# shunts_and_amplifiers.net
KiCad netlist of a schematic drawn in Altium Designer
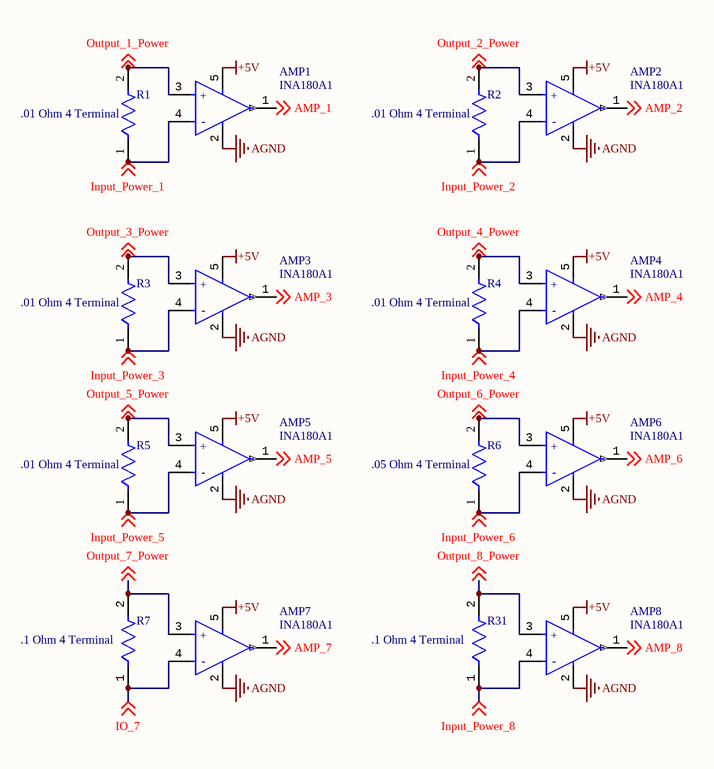
[diagram p0: shunts_and_amplifiers.SchDoc]

(export (version "E")
  (design (tool "Eeschema 10.0.6"))
  (components
    (comp (ref "AMP1")
      (value "INA180A1")
      (footprint "FP-DBV0005A-IPC_A")
      (description "IC CURR SENSE 1 CIRCUIT SOT23-5")
      (libsource (lib "Altium Content Vault") (part "0a55cf1a948ad01a3239aec1b7efad0"))
    )
    (comp (ref "AMP2")
      (value "INA180A1")
      (footprint "FP-DBV0005A-IPC_A")
      (description "IC CURR SENSE 1 CIRCUIT SOT23-5")
      (libsource (lib "Altium Content Vault") (part "0a55cf1a948ad01a3239aec1b7efad0"))
    )
    (comp (ref "AMP3")
      (value "INA180A1")
      (footprint "FP-DBV0005A-IPC_A")
      (description "IC CURR SENSE 1 CIRCUIT SOT23-5")
      (libsource (lib "Altium Content Vault") (part "0a55cf1a948ad01a3239aec1b7efad0"))
    )
    (comp (ref "AMP4")
      (value "INA180A1")
      (footprint "FP-DBV0005A-IPC_A")
      (description "IC CURR SENSE 1 CIRCUIT SOT23-5")
      (libsource (lib "Altium Content Vault") (part "0a55cf1a948ad01a3239aec1b7efad0"))
    )
    (comp (ref "AMP5")
      (value "INA180A1")
      (footprint "FP-DBV0005A-IPC_A")
      (description "IC CURR SENSE 1 CIRCUIT SOT23-5")
      (libsource (lib "Altium Content Vault") (part "0a55cf1a948ad01a3239aec1b7efad0"))
    )
    (comp (ref "AMP6")
      (value "INA180A1")
      (footprint "FP-DBV0005A-IPC_A")
      (description "IC CURR SENSE 1 CIRCUIT SOT23-5")
      (libsource (lib "Altium Content Vault") (part "0a55cf1a948ad01a3239aec1b7efad0"))
    )
    (comp (ref "AMP7")
      (value "INA180A1")
      (footprint "FP-DBV0005A-IPC_A")
      (description "IC CURR SENSE 1 CIRCUIT SOT23-5")
      (libsource (lib "Altium Content Vault") (part "0a55cf1a948ad01a3239aec1b7efad0"))
    )
    (comp (ref "AMP8")
      (value "INA180A1")
      (footprint "FP-DBV0005A-IPC_A")
      (description "IC CURR SENSE 1 CIRCUIT SOT23-5")
      (libsource (lib "Altium Content Vault") (part "0a55cf1a948ad01a3239aec1b7efad0"))
    )
    (comp (ref "R1")
      (value ".01 Ohm 4 Terminal")
      (footprint "FP-WSR3-MFG")
      (description "WSR3R0500FEA Res Metal Strip 4527 0.05 Ohm 1% 3W ±75ppm/°C Molded SMD SMD Embossed Plastic T/R")
      (fields (field (name "TOLERANCE") "1%"))
      (libsource (lib "Altium Content Vault") (part "1029c3af85768c4190bb7ad29bc67b5"))
    )
    (comp (ref "R2")
      (value ".01 Ohm 4 Terminal")
      (footprint "FP-WSR3-MFG")
      (description "WSR3R0500FEA Res Metal Strip 4527 0.05 Ohm 1% 3W ±75ppm/°C Molded SMD SMD Embossed Plastic T/R")
      (fields (field (name "TOLERANCE") "1%"))
      (libsource (lib "Altium Content Vault") (part "1029c3af85768c4190bb7ad29bc67b5"))
    )
    (comp (ref "R3")
      (value ".01 Ohm 4 Terminal")
      (footprint "FP-WSR3-MFG")
      (description "WSR3R0500FEA Res Metal Strip 4527 0.05 Ohm 1% 3W ±75ppm/°C Molded SMD SMD Embossed Plastic T/R")
      (fields (field (name "TOLERANCE") "1%"))
      (libsource (lib "Altium Content Vault") (part "1029c3af85768c4190bb7ad29bc67b5"))
    )
    (comp (ref "R4")
      (value ".01 Ohm 4 Terminal")
      (footprint "FP-WSR3-MFG")
      (description "WSR3R0500FEA Res Metal Strip 4527 0.05 Ohm 1% 3W ±75ppm/°C Molded SMD SMD Embossed Plastic T/R")
      (fields (field (name "TOLERANCE") "1%"))
      (libsource (lib "Altium Content Vault") (part "1029c3af85768c4190bb7ad29bc67b5"))
    )
    (comp (ref "R5")
      (value ".01 Ohm 4 Terminal")
      (footprint "FP-WSR3-MFG")
      (description "WSR3R0500FEA Res Metal Strip 4527 0.05 Ohm 1% 3W ±75ppm/°C Molded SMD SMD Embossed Plastic T/R")
      (fields (field (name "TOLERANCE") "1%"))
      (libsource (lib "Altium Content Vault") (part "1029c3af85768c4190bb7ad29bc67b5"))
    )
    (comp (ref "R6")
      (value ".05 Ohm 4 Terminal")
      (footprint "FP-WSR3-MFG")
      (description "WSR3R0500FEA Res Metal Strip 4527 0.05 Ohm 1% 3W ±75ppm/°C Molded SMD SMD Embossed Plastic T/R")
      (fields (field (name "TOLERANCE") "1%"))
      (libsource (lib "Altium Content Vault") (part "1029c3af85768c4190bb7ad29bc67b5"))
    )
    (comp (ref "R7")
      (value ".1 Ohm 4 Terminal")
      (footprint "FP-WSR-MFG")
      (description "RES 0.1 OHM 1% 3W 4527\r\nWSR3R1000FEK")
      (fields (field (name "MANUFACTURER PART NUMBER") "WSR3R1000FEK") (field (name "TOLERANCE") "1%"))
      (libsource (lib "Altium Content Vault") (part "1029c3af85768c4190bb7ad29bc67b5"))
    )
    (comp (ref "R31")
      (value ".1 Ohm 4 Terminal")
      (footprint "FP-WSR-MFG")
      (description "RES 0.1 OHM 1% 3W 4527\r\nWSR3R1000FEK")
      (fields (field (name "MANUFACTURER PART NUMBER") "WSR3R1000FEK") (field (name "TOLERANCE") "1%"))
      (libsource (lib "Altium Content Vault") (part "1029c3af85768c4190bb7ad29bc67b5"))
    )
  )
  (nets
    (net (code "1") (name "+5V") (class "Default")
      (node (ref "AMP1") (pin "5") (pinfunction "VS_5") (pintype "power_in"))
      (node (ref "AMP2") (pin "5") (pinfunction "VS_5") (pintype "power_in"))
      (node (ref "AMP3") (pin "5") (pinfunction "VS_5") (pintype "power_in"))
      (node (ref "AMP4") (pin "5") (pinfunction "VS_5") (pintype "power_in"))
      (node (ref "AMP5") (pin "5") (pinfunction "VS_5") (pintype "power_in"))
      (node (ref "AMP6") (pin "5") (pinfunction "VS_5") (pintype "power_in"))
      (node (ref "AMP7") (pin "5") (pinfunction "VS_5") (pintype "power_in"))
      (node (ref "AMP8") (pin "5") (pinfunction "VS_5") (pintype "power_in"))
    )
    (net (code "2") (name "AGND") (class "Default")
      (node (ref "AMP1") (pin "2") (pinfunction "GND_2") (pintype "power_in"))
      (node (ref "AMP2") (pin "2") (pinfunction "GND_2") (pintype "power_in"))
      (node (ref "AMP3") (pin "2") (pinfunction "GND_2") (pintype "power_in"))
      (node (ref "AMP4") (pin "2") (pinfunction "GND_2") (pintype "power_in"))
      (node (ref "AMP5") (pin "2") (pinfunction "GND_2") (pintype "power_in"))
      (node (ref "AMP6") (pin "2") (pinfunction "GND_2") (pintype "power_in"))
      (node (ref "AMP7") (pin "2") (pinfunction "GND_2") (pintype "power_in"))
      (node (ref "AMP8") (pin "2") (pinfunction "GND_2") (pintype "power_in"))
    )
    (net (code "3") (name "AMP_1") (class "Default")
      (node (ref "AMP1") (pin "1") (pinfunction "OUT_1") (pintype "output"))
    )
    (net (code "4") (name "AMP_2") (class "Default")
      (node (ref "AMP2") (pin "1") (pinfunction "OUT_1") (pintype "output"))
    )
    (net (code "5") (name "AMP_3") (class "Default")
      (node (ref "AMP3") (pin "1") (pinfunction "OUT_1") (pintype "output"))
    )
    (net (code "6") (name "AMP_4") (class "Default")
      (node (ref "AMP4") (pin "1") (pinfunction "OUT_1") (pintype "output"))
    )
    (net (code "7") (name "AMP_5") (class "Default")
      (node (ref "AMP5") (pin "1") (pinfunction "OUT_1") (pintype "output"))
    )
    (net (code "8") (name "AMP_6") (class "Default")
      (node (ref "AMP6") (pin "1") (pinfunction "OUT_1") (pintype "output"))
    )
    (net (code "9") (name "AMP_7") (class "Default")
      (node (ref "AMP7") (pin "1") (pinfunction "OUT_1") (pintype "output"))
    )
    (net (code "10") (name "AMP_8") (class "Default")
      (node (ref "AMP8") (pin "1") (pinfunction "OUT_1") (pintype "output"))
    )
    (net (code "11") (name "IO_7") (class "Default")
      (node (ref "AMP7") (pin "4") (pinfunction "IN-_4") (pintype "tri_state"))
      (node (ref "R7") (pin "1") (pinfunction "1_1") (pintype "passive"))
    )
    (net (code "12") (name "Input_Power_1") (class "Default")
      (node (ref "AMP1") (pin "4") (pinfunction "IN-_4") (pintype "tri_state"))
      (node (ref "R1") (pin "1") (pinfunction "1_1") (pintype "passive"))
    )
    (net (code "13") (name "Input_Power_2") (class "Default")
      (node (ref "AMP2") (pin "4") (pinfunction "IN-_4") (pintype "tri_state"))
      (node (ref "R2") (pin "1") (pinfunction "1_1") (pintype "passive"))
    )
    (net (code "14") (name "Input_Power_3") (class "Default")
      (node (ref "AMP3") (pin "4") (pinfunction "IN-_4") (pintype "tri_state"))
      (node (ref "R3") (pin "1") (pinfunction "1_1") (pintype "passive"))
    )
    (net (code "15") (name "Input_Power_4") (class "Default")
      (node (ref "AMP4") (pin "4") (pinfunction "IN-_4") (pintype "tri_state"))
      (node (ref "R4") (pin "1") (pinfunction "1_1") (pintype "passive"))
    )
    (net (code "16") (name "Input_Power_5") (class "Default")
      (node (ref "AMP5") (pin "4") (pinfunction "IN-_4") (pintype "tri_state"))
      (node (ref "R5") (pin "1") (pinfunction "1_1") (pintype "passive"))
    )
    (net (code "17") (name "Input_Power_6") (class "Default")
      (node (ref "AMP6") (pin "4") (pinfunction "IN-_4") (pintype "tri_state"))
      (node (ref "R6") (pin "1") (pinfunction "1_1") (pintype "passive"))
    )
    (net (code "18") (name "Input_Power_8") (class "Default")
      (node (ref "AMP8") (pin "4") (pinfunction "IN-_4") (pintype "tri_state"))
      (node (ref "R31") (pin "1") (pinfunction "1_1") (pintype "passive"))
    )
    (net (code "19") (name "Output_1_Power") (class "Default")
      (node (ref "AMP1") (pin "3") (pinfunction "IN+_3") (pintype "tri_state"))
      (node (ref "R1") (pin "2") (pinfunction "2_2") (pintype "passive"))
    )
    (net (code "20") (name "Output_2_Power") (class "Default")
      (node (ref "AMP2") (pin "3") (pinfunction "IN+_3") (pintype "tri_state"))
      (node (ref "R2") (pin "2") (pinfunction "2_2") (pintype "passive"))
    )
    (net (code "21") (name "Output_3_Power") (class "Default")
      (node (ref "AMP3") (pin "3") (pinfunction "IN+_3") (pintype "tri_state"))
      (node (ref "R3") (pin "2") (pinfunction "2_2") (pintype "passive"))
    )
    (net (code "22") (name "Output_4_Power") (class "Default")
      (node (ref "AMP4") (pin "3") (pinfunction "IN+_3") (pintype "tri_state"))
      (node (ref "R4") (pin "2") (pinfunction "2_2") (pintype "passive"))
    )
    (net (code "23") (name "Output_5_Power") (class "Default")
      (node (ref "AMP5") (pin "3") (pinfunction "IN+_3") (pintype "tri_state"))
      (node (ref "R5") (pin "2") (pinfunction "2_2") (pintype "passive"))
    )
    (net (code "24") (name "Output_6_Power") (class "Default")
      (node (ref "AMP6") (pin "3") (pinfunction "IN+_3") (pintype "tri_state"))
      (node (ref "R6") (pin "2") (pinfunction "2_2") (pintype "passive"))
    )
    (net (code "25") (name "Output_7_Power") (class "Default")
      (node (ref "AMP7") (pin "3") (pinfunction "IN+_3") (pintype "tri_state"))
      (node (ref "R7") (pin "2") (pinfunction "2_2") (pintype "passive"))
    )
    (net (code "26") (name "Output_8_Power") (class "Default")
      (node (ref "AMP8") (pin "3") (pinfunction "IN+_3") (pintype "tri_state"))
      (node (ref "R31") (pin "2") (pinfunction "2_2") (pintype "passive"))
    )
  )
)
